# Schematic.net
KiCad netlist of a schematic drawn in EAGLE
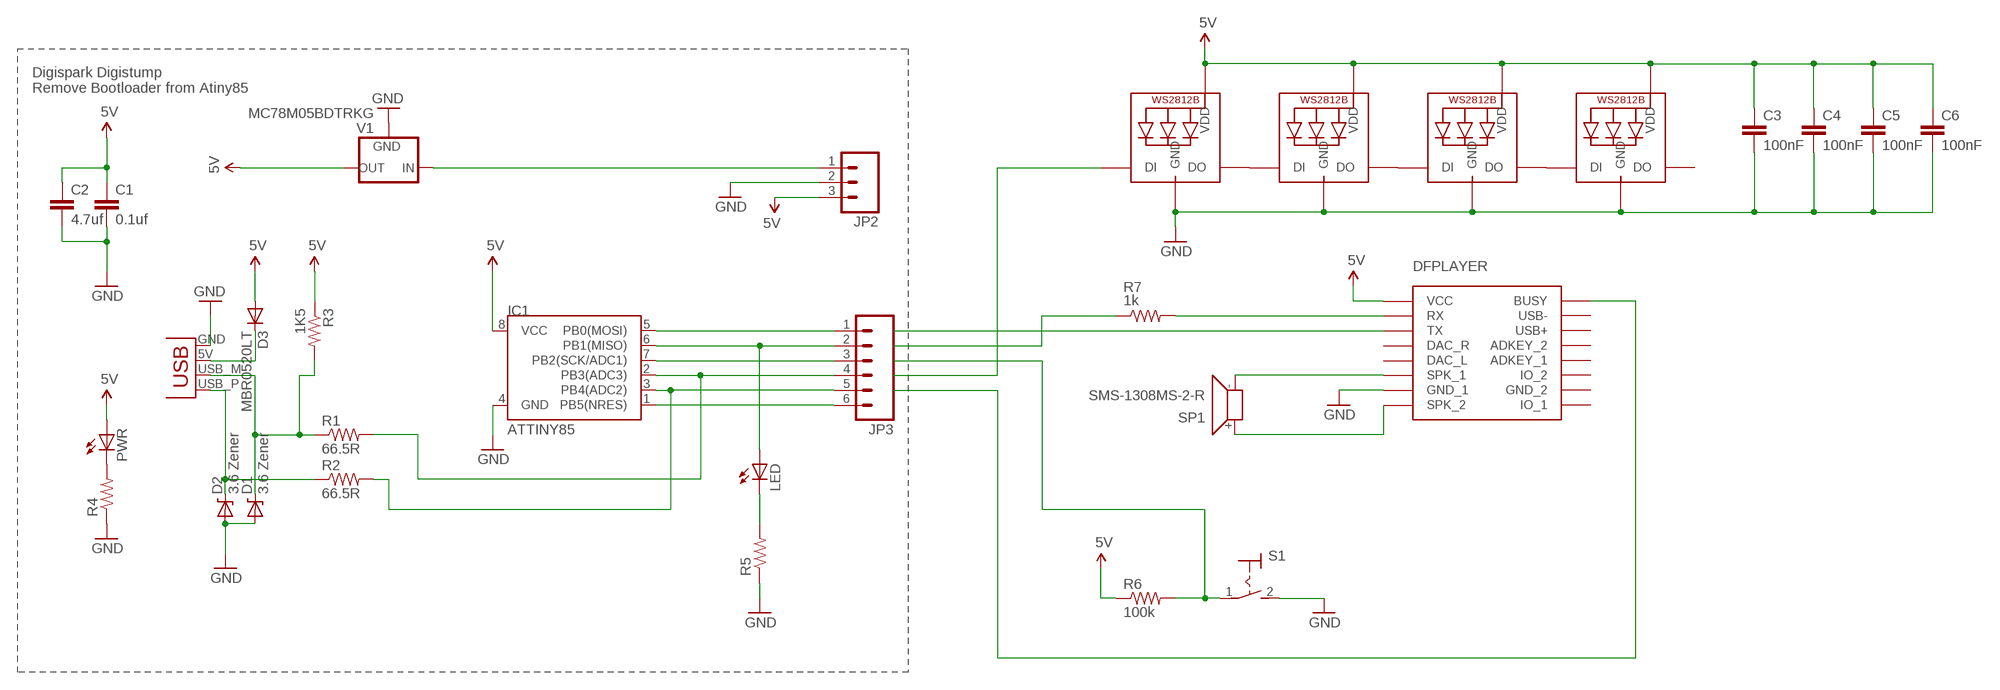
[diagram p0: schematic, sheet 1]

(export (version "E")
  (design (tool "Eeschema 10.0.6"))
  (components
    (comp (ref "C1")
      (value "0.1uf")
      (footprint "eagle-import:0402-CAP")
      (libsource (lib "eagle-import") (part "CAP0402-CAP"))
    )
    (comp (ref "C2")
      (value "4.7uf")
      (footprint "eagle-import:0805")
      (libsource (lib "eagle-import") (part "CAP0805"))
    )
    (comp (ref "C3")
      (value "100nF")
      (footprint "eagle-import:C102-054X133")
      (libsource (lib "eagle-import") (part "C-EU102-054X133"))
    )
    (comp (ref "C4")
      (value "100nF")
      (footprint "eagle-import:C102-054X133")
      (libsource (lib "eagle-import") (part "C-EU102-054X133"))
    )
    (comp (ref "C5")
      (value "100nF")
      (footprint "eagle-import:C102-054X133")
      (libsource (lib "eagle-import") (part "C-EU102-054X133"))
    )
    (comp (ref "C6")
      (value "100nF")
      (footprint "eagle-import:C102-054X133")
      (libsource (lib "eagle-import") (part "C-EU102-054X133"))
    )
    (comp (ref "D1")
      (value "3.6 Zener")
      (footprint "eagle-import:SOD-323")
      (libsource (lib "eagle-import") (part "DIODE-ZENER-BZT52"))
    )
    (comp (ref "D2")
      (value "3.6 Zener")
      (footprint "eagle-import:SOD-323")
      (libsource (lib "eagle-import") (part "DIODE-ZENER-BZT52"))
    )
    (comp (ref "D3")
      (value "MBR0520LT")
      (footprint "eagle-import:SOD123")
      (libsource (lib "eagle-import") (part "MBR0520LT"))
    )
    (comp (ref "IC1")
      (value "ATTINY85")
      (footprint "eagle-import:SO08-EIAJ")
      (libsource (lib "eagle-import") (part "ATTINY45"))
    )
    (comp (ref "JP2")
      (value "M03PTH")
      (footprint "eagle-import:1X03")
      (libsource (lib "eagle-import") (part "M03PTH"))
    )
    (comp (ref "JP3")
      (value "M06SIP")
      (footprint "eagle-import:1X06")
      (libsource (lib "eagle-import") (part "M06SIP"))
    )
    (comp (ref "LED")
      (value "LED0603")
      (footprint "eagle-import:LED-0603")
      (libsource (lib "eagle-import") (part "LED0603"))
    )
    (comp (ref "LED1")
      (value "WS2812B3535")
      (footprint "eagle-import:LED3535")
      (libsource (lib "eagle-import") (part "WS2812B3535"))
    )
    (comp (ref "LED2")
      (value "WS2812B3535")
      (footprint "eagle-import:LED3535")
      (libsource (lib "eagle-import") (part "WS2812B3535"))
    )
    (comp (ref "LED3")
      (value "WS2812B3535")
      (footprint "eagle-import:LED3535")
      (libsource (lib "eagle-import") (part "WS2812B3535"))
    )
    (comp (ref "LED4")
      (value "WS2812B3535")
      (footprint "eagle-import:LED3535")
      (libsource (lib "eagle-import") (part "WS2812B3535"))
    )
    (comp (ref "PWR")
      (value "LED0603")
      (footprint "eagle-import:LED-0603")
      (libsource (lib "eagle-import") (part "LED0603"))
    )
    (comp (ref "R1")
      (value "66.5R")
      (footprint "eagle-import:0402-RES")
      (libsource (lib "eagle-import") (part "RESISTOR0402-RES"))
    )
    (comp (ref "R2")
      (value "66.5R")
      (footprint "eagle-import:0402-RES")
      (libsource (lib "eagle-import") (part "RESISTOR0402-RES"))
    )
    (comp (ref "R3")
      (value "1K5")
      (footprint "eagle-import:0402-RES")
      (libsource (lib "eagle-import") (part "RESISTOR0402-RES"))
    )
    (comp (ref "R4")
      (value "RESISTOR0402-RES")
      (footprint "eagle-import:0402-RES")
      (libsource (lib "eagle-import") (part "RESISTOR0402-RES"))
    )
    (comp (ref "R5")
      (value "RESISTOR0402-RES")
      (footprint "eagle-import:0402-RES")
      (libsource (lib "eagle-import") (part "RESISTOR0402-RES"))
    )
    (comp (ref "R6")
      (value "100k")
      (footprint "eagle-import:0402-RES")
      (libsource (lib "eagle-import") (part "RESISTOR0402-RES"))
    )
    (comp (ref "R7")
      (value "1k")
      (footprint "eagle-import:0402-RES")
      (libsource (lib "eagle-import") (part "RESISTOR0402-RES"))
    )
    (comp (ref "S1")
      (value "MS243")
      (footprint "eagle-import:MS243")
      (libsource (lib "eagle-import") (part "MS243"))
    )
    (comp (ref "SP1")
      (value "SMS-1308MS-2-R")
      (footprint "eagle-import:SMS-1308MS-2-R")
      (libsource (lib "eagle-import") (part "SMS-1308MS-2-R"))
    )
    (comp (ref "U$8")
      (value "DF")
      (footprint "eagle-import:DFPLAYER")
      (libsource (lib "eagle-import") (part "DFPLAYER"))
    )
    (comp (ref "V1")
      (value "MC78M05BDTRKG")
      (footprint "eagle-import:DPACK")
      (libsource (lib "eagle-import") (part "LP2950?CDT-3.0"))
    )
    (comp (ref "X1")
      (value "USBPCB")
      (footprint "eagle-import:USB-A-PCB")
      (libsource (lib "eagle-import") (part "USBPCB"))
    )
  )
  (nets
    (net (code "1") (name "5V") (class "Default")
      (node (ref "C1") (pin "1") (pinfunction "1_1") (pintype "passive"))
      (node (ref "C2") (pin "1") (pinfunction "1_1") (pintype "passive"))
      (node (ref "C3") (pin "1") (pinfunction "1_1") (pintype "passive"))
      (node (ref "C4") (pin "1") (pinfunction "1_1") (pintype "passive"))
      (node (ref "C5") (pin "1") (pinfunction "1_1") (pintype "passive"))
      (node (ref "C6") (pin "1") (pinfunction "1_1") (pintype "passive"))
      (node (ref "D3") (pin "A") (pinfunction "A_A") (pintype "passive"))
      (node (ref "IC1") (pin "8") (pinfunction "VCC_8") (pintype "bidirectional"))
      (node (ref "JP2") (pin "3") (pinfunction "3_3") (pintype "passive"))
      (node (ref "LED1") (pin "2") (pinfunction "VDD_2") (pintype "power_in"))
      (node (ref "LED2") (pin "2") (pinfunction "VDD_2") (pintype "power_in"))
      (node (ref "LED3") (pin "2") (pinfunction "VDD_2") (pintype "power_in"))
      (node (ref "LED4") (pin "2") (pinfunction "VDD_2") (pintype "power_in"))
      (node (ref "PWR") (pin "A") (pinfunction "A_A") (pintype "passive"))
      (node (ref "R3") (pin "1") (pinfunction "1_1") (pintype "passive"))
      (node (ref "R6") (pin "1") (pinfunction "1_1") (pintype "passive"))
      (node (ref "U$8") (pin "VCC") (pinfunction "VCC_VCC") (pintype "bidirectional"))
      (node (ref "V1") (pin "3") (pinfunction "OUT_3") (pintype "passive"))
    )
    (net (code "2") (name "GND") (class "Default")
      (node (ref "C1") (pin "2") (pinfunction "2_2") (pintype "passive"))
      (node (ref "C2") (pin "2") (pinfunction "2_2") (pintype "passive"))
      (node (ref "C3") (pin "2") (pinfunction "2_2") (pintype "passive"))
      (node (ref "C4") (pin "2") (pinfunction "2_2") (pintype "passive"))
      (node (ref "C5") (pin "2") (pinfunction "2_2") (pintype "passive"))
      (node (ref "C6") (pin "2") (pinfunction "2_2") (pintype "passive"))
      (node (ref "D1") (pin "2") (pinfunction "A_2") (pintype "passive"))
      (node (ref "D2") (pin "2") (pinfunction "A_2") (pintype "passive"))
      (node (ref "IC1") (pin "4") (pinfunction "GND_4") (pintype "bidirectional"))
      (node (ref "JP2") (pin "2") (pinfunction "2_2") (pintype "passive"))
      (node (ref "LED1") (pin "4") (pinfunction "GND_4") (pintype "power_in"))
      (node (ref "LED2") (pin "4") (pinfunction "GND_4") (pintype "power_in"))
      (node (ref "LED3") (pin "4") (pinfunction "GND_4") (pintype "power_in"))
      (node (ref "LED4") (pin "4") (pinfunction "GND_4") (pintype "power_in"))
      (node (ref "R4") (pin "1") (pinfunction "1_1") (pintype "passive"))
      (node (ref "R5") (pin "1") (pinfunction "1_1") (pintype "passive"))
      (node (ref "S1") (pin "2") (pinfunction "S_2") (pintype "passive"))
      (node (ref "U$8") (pin "GND_1") (pinfunction "GND_1_GND_1") (pintype "bidirectional"))
      (node (ref "V1") (pin "4") (pinfunction "GND_4") (pintype "input"))
      (node (ref "X1") (pin "GND") (pinfunction "GND_GND") (pintype "bidirectional"))
    )
    (net (code "3") (name "Net-(D1-C)") (class "Default")
      (node (ref "D1") (pin "1") (pinfunction "C_1") (pintype "passive"))
      (node (ref "R1") (pin "1") (pinfunction "1_1") (pintype "passive"))
      (node (ref "R3") (pin "2") (pinfunction "2_2") (pintype "passive"))
      (node (ref "X1") (pin "USB_M") (pinfunction "D-_USB_M") (pintype "bidirectional"))
    )
    (net (code "4") (name "Net-(D2-C)") (class "Default")
      (node (ref "D2") (pin "1") (pinfunction "C_1") (pintype "passive"))
      (node (ref "R2") (pin "1") (pinfunction "1_1") (pintype "passive"))
      (node (ref "X1") (pin "USB_P") (pinfunction "D+_USB_P") (pintype "bidirectional"))
    )
    (net (code "5") (name "Net-(IC1-PB0(MOSI))") (class "Default")
      (node (ref "IC1") (pin "5") (pinfunction "PB0(MOSI)_5") (pintype "bidirectional"))
      (node (ref "JP3") (pin "1") (pinfunction "1_1") (pintype "passive"))
    )
    (net (code "6") (name "Net-(IC1-PB1(MISO))") (class "Default")
      (node (ref "IC1") (pin "6") (pinfunction "PB1(MISO)_6") (pintype "bidirectional"))
      (node (ref "JP3") (pin "2") (pinfunction "2_2") (pintype "passive"))
      (node (ref "LED") (pin "A") (pinfunction "A_A") (pintype "passive"))
    )
    (net (code "7") (name "Net-(IC1-PB2(SCK{slash}ADC1))") (class "Default")
      (node (ref "IC1") (pin "7") (pinfunction "PB2(SCK/ADC1)_7") (pintype "bidirectional"))
      (node (ref "JP3") (pin "3") (pinfunction "3_3") (pintype "passive"))
    )
    (net (code "8") (name "Net-(IC1-PB3(ADC3))") (class "Default")
      (node (ref "IC1") (pin "2") (pinfunction "PB3(ADC3)_2") (pintype "bidirectional"))
      (node (ref "JP3") (pin "4") (pinfunction "4_4") (pintype "passive"))
      (node (ref "R1") (pin "2") (pinfunction "2_2") (pintype "passive"))
    )
    (net (code "9") (name "Net-(IC1-PB4(ADC2))") (class "Default")
      (node (ref "IC1") (pin "3") (pinfunction "PB4(ADC2)_3") (pintype "bidirectional"))
      (node (ref "JP3") (pin "5") (pinfunction "5_5") (pintype "passive"))
      (node (ref "R2") (pin "2") (pinfunction "2_2") (pintype "passive"))
    )
    (net (code "10") (name "Net-(IC1-PB5(NRES))") (class "Default")
      (node (ref "IC1") (pin "1") (pinfunction "PB5(NRES)_1") (pintype "bidirectional"))
      (node (ref "JP3") (pin "6") (pinfunction "6_6") (pintype "passive"))
    )
    (net (code "11") (name "Net-(LED-PadC)") (class "Default")
      (node (ref "LED") (pin "C") (pinfunction "C_C") (pintype "passive"))
      (node (ref "R5") (pin "2") (pinfunction "2_2") (pintype "passive"))
    )
    (net (code "12") (name "Net-(LED1-DO)") (class "Default")
      (node (ref "LED1") (pin "3") (pinfunction "DO_3") (pintype "output"))
      (node (ref "LED2") (pin "1") (pinfunction "DI_1") (pintype "input"))
    )
    (net (code "13") (name "Net-(LED2-DO)") (class "Default")
      (node (ref "LED2") (pin "3") (pinfunction "DO_3") (pintype "output"))
      (node (ref "LED3") (pin "1") (pinfunction "DI_1") (pintype "input"))
    )
    (net (code "14") (name "Net-(LED3-DO)") (class "Default")
      (node (ref "LED3") (pin "3") (pinfunction "DO_3") (pintype "output"))
      (node (ref "LED4") (pin "1") (pinfunction "DI_1") (pintype "input"))
    )
    (net (code "15") (name "Net-(PWR-PadC)") (class "Default")
      (node (ref "PWR") (pin "C") (pinfunction "C_C") (pintype "passive"))
      (node (ref "R4") (pin "2") (pinfunction "2_2") (pintype "passive"))
    )
    (net (code "16") (name "Net-(R7-Pad2)") (class "Default")
      (node (ref "R7") (pin "2") (pinfunction "2_2") (pintype "passive"))
      (node (ref "U$8") (pin "RX") (pinfunction "RX_RX") (pintype "bidirectional"))
    )
    (net (code "17") (name "Net-(S1-P)") (class "Default")
      (node (ref "R6") (pin "2") (pinfunction "2_2") (pintype "passive"))
      (node (ref "S1") (pin "1") (pinfunction "P_1") (pintype "passive"))
    )
    (net (code "18") (name "Net-(SP1-1)") (class "Default")
      (node (ref "SP1") (pin "+") (pinfunction "1_+") (pintype "passive"))
      (node (ref "U$8") (pin "SPK2") (pinfunction "SPK_2_SPK2") (pintype "bidirectional"))
    )
    (net (code "19") (name "Net-(SP1-2)") (class "Default")
      (node (ref "SP1") (pin "-") (pinfunction "2_-") (pintype "passive"))
      (node (ref "U$8") (pin "SPK1") (pinfunction "SPK_1_SPK1") (pintype "bidirectional"))
    )
    (net (code "20") (name "Net-(V1-IN)") (class "Default")
      (node (ref "JP2") (pin "1") (pinfunction "1_1") (pintype "passive"))
      (node (ref "V1") (pin "1") (pinfunction "IN_1") (pintype "input"))
    )
    (net (code "21") (name "Net-(X1-VBUS)") (class "Default")
      (node (ref "D3") (pin "C") (pinfunction "C_C") (pintype "passive"))
      (node (ref "X1") (pin "5V") (pinfunction "VBUS_5V") (pintype "bidirectional"))
    )
    (net (code "22") (name "unconnected-(LED1-DI-Pad1)") (class "Default")
      (node (ref "LED1") (pin "1") (pinfunction "DI_1") (pintype "input"))
    )
    (net (code "23") (name "unconnected-(LED4-DO-Pad3)") (class "Default")
      (node (ref "LED4") (pin "3") (pinfunction "DO_3") (pintype "output"))
    )
    (net (code "24") (name "unconnected-(R7-Pad1)") (class "Default")
      (node (ref "R7") (pin "1") (pinfunction "1_1") (pintype "passive"))
    )
    (net (code "25") (name "unconnected-(U$8-ADKEY_1-PadADKEY1)") (class "Default")
      (node (ref "U$8") (pin "ADKEY1") (pinfunction "ADKEY_1_ADKEY1") (pintype "bidirectional"))
    )
    (net (code "26") (name "unconnected-(U$8-ADKEY_2-PadADKEY2)") (class "Default")
      (node (ref "U$8") (pin "ADKEY2") (pinfunction "ADKEY_2_ADKEY2") (pintype "bidirectional"))
    )
    (net (code "27") (name "unconnected-(U$8-IO_1-PadIO1)") (class "Default")
      (node (ref "U$8") (pin "IO1") (pinfunction "IO_1_IO1") (pintype "bidirectional"))
    )
    (net (code "28") (name "unconnected-(U$8-IO_2-PadIO2)") (class "Default")
      (node (ref "U$8") (pin "IO2") (pinfunction "IO_2_IO2") (pintype "bidirectional"))
    )
    (net (code "29") (name "unconnected-(U$8-PadBUSY)") (class "Default")
      (node (ref "U$8") (pin "BUSY") (pinfunction "BUSY_BUSY") (pintype "bidirectional"))
    )
    (net (code "30") (name "unconnected-(U$8-PadDAC_L)") (class "Default")
      (node (ref "U$8") (pin "DAC_L") (pinfunction "DAC_L_DAC_L") (pintype "bidirectional"))
    )
    (net (code "31") (name "unconnected-(U$8-PadDAC_R)") (class "Default")
      (node (ref "U$8") (pin "DAC_R") (pinfunction "DAC_R_DAC_R") (pintype "bidirectional"))
    )
    (net (code "32") (name "unconnected-(U$8-PadGND_2)") (class "Default")
      (node (ref "U$8") (pin "GND_2") (pinfunction "GND_2_GND_2") (pintype "bidirectional"))
    )
    (net (code "33") (name "unconnected-(U$8-PadTX)") (class "Default")
      (node (ref "U$8") (pin "TX") (pinfunction "TX_TX") (pintype "bidirectional"))
    )
    (net (code "34") (name "unconnected-(U$8-PadUSB+)") (class "Default")
      (node (ref "U$8") (pin "USB+") (pinfunction "USB+_USB+") (pintype "bidirectional"))
    )
    (net (code "35") (name "unconnected-(U$8-PadUSB-)") (class "Default")
      (node (ref "U$8") (pin "USB-") (pinfunction "USB-_USB-") (pintype "bidirectional"))
    )
  )
)
